# DPPXHK_IO.net
KiCad netlist of a schematic drawn in Altium Designer
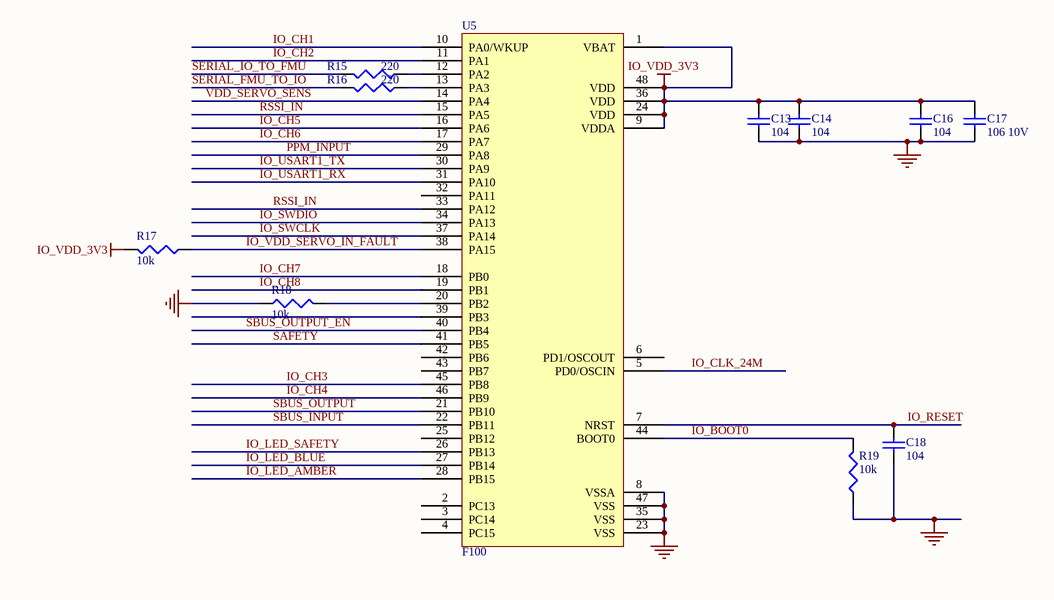
[diagram p0: DPPXHK_IO.SCHDOC]

(export (version "E")
  (design (tool "Eeschema 10.0.6"))
  (components
    (comp (ref "C13")
      (value "104")
      (footprint "LC0402")
      (description "Capacitor (Semiconductor SIM Model)")
      (fields (field (name "PUBLISHER") "Altium Limited"))
      (libsource (lib "Miscellaneous Devices") (part "Cap Semi"))
    )
    (comp (ref "C14")
      (value "104")
      (footprint "LC0402")
      (description "Capacitor (Semiconductor SIM Model)")
      (fields (field (name "PUBLISHER") "Altium Limited"))
      (libsource (lib "Miscellaneous Devices") (part "Cap Semi"))
    )
    (comp (ref "C16")
      (value "104")
      (footprint "LC0402")
      (description "Capacitor (Semiconductor SIM Model)")
      (fields (field (name "PUBLISHER") "Altium Limited"))
      (libsource (lib "Miscellaneous Devices") (part "Cap Semi"))
    )
    (comp (ref "C17")
      (value "106 10V")
      (footprint "LC0402")
      (description "Capacitor (Semiconductor SIM Model)")
      (fields (field (name "PUBLISHER") "Altium Limited"))
      (libsource (lib "Miscellaneous Devices") (part "Cap Semi"))
    )
    (comp (ref "C18")
      (value "104")
      (footprint "LC0402")
      (description "Capacitor (Semiconductor SIM Model)")
      (fields (field (name "PUBLISHER") "Altium Limited"))
      (libsource (lib "Miscellaneous Devices") (part "Cap Semi"))
    )
    (comp (ref "R15")
      (value "220")
      (footprint "0402R")
      (description "Resistor")
      (fields (field (name "PUBLISHER") "Altium Limited"))
      (libsource (lib "Miscellaneous Devices") (part "Res3"))
    )
    (comp (ref "R16")
      (value "220")
      (footprint "0402R")
      (description "Resistor")
      (fields (field (name "PUBLISHER") "Altium Limited"))
      (libsource (lib "Miscellaneous Devices") (part "Res3"))
    )
    (comp (ref "R17")
      (value "10k")
      (footprint "0402R")
      (description "Resistor")
      (fields (field (name "PUBLISHER") "Altium Limited"))
      (libsource (lib "Miscellaneous Devices") (part "Res3"))
    )
    (comp (ref "R18")
      (value "10k")
      (footprint "0402R")
      (description "Resistor")
      (fields (field (name "PUBLISHER") "Altium Limited"))
      (libsource (lib "Miscellaneous Devices") (part "Res3"))
    )
    (comp (ref "R19")
      (value "10k")
      (footprint "0402R")
      (description "Resistor")
      (fields (field (name "PUBLISHER") "Altium Limited"))
      (libsource (lib "Miscellaneous Devices") (part "Res3"))
    )
    (comp (ref "U5") (value "F100") (footprint "LQFP48_ST") (libsource (lib "PXHK") (part "F100")))
  )
  (nets
    (net (code "1") (name "/IO_BOOT0") (class "Default")
      (node (ref "R19") (pin "2") (pinfunction "2_2") (pintype "passive"))
      (node (ref "U5") (pin "44") (pinfunction "BOOT0_44") (pintype "passive"))
    )
    (net (code "2") (name "/IO_CH1") (class "Default")
      (node (ref "U5") (pin "10") (pinfunction "PA0/WKUP_10") (pintype "passive"))
    )
    (net (code "3") (name "/IO_CH2") (class "Default")
      (node (ref "U5") (pin "11") (pinfunction "PA1_11") (pintype "passive"))
    )
    (net (code "4") (name "/IO_CH3") (class "Default")
      (node (ref "U5") (pin "45") (pinfunction "PB8_45") (pintype "passive"))
    )
    (net (code "5") (name "/IO_CH4") (class "Default")
      (node (ref "U5") (pin "46") (pinfunction "PB9_46") (pintype "passive"))
    )
    (net (code "6") (name "/IO_CH5") (class "Default")
      (node (ref "U5") (pin "16") (pinfunction "PA6_16") (pintype "passive"))
    )
    (net (code "7") (name "/IO_CH6") (class "Default")
      (node (ref "U5") (pin "17") (pinfunction "PA7_17") (pintype "passive"))
    )
    (net (code "8") (name "/IO_CH7") (class "Default")
      (node (ref "U5") (pin "18") (pinfunction "PB0_18") (pintype "passive"))
    )
    (net (code "9") (name "/IO_CH8") (class "Default")
      (node (ref "U5") (pin "19") (pinfunction "PB1_19") (pintype "passive"))
    )
    (net (code "10") (name "/IO_CLK_24M") (class "Default")
      (node (ref "U5") (pin "5") (pinfunction "PD0/OSCIN_5") (pintype "passive"))
    )
    (net (code "11") (name "/IO_LED_AMBER") (class "Default")
      (node (ref "U5") (pin "28") (pinfunction "PB15_28") (pintype "passive"))
    )
    (net (code "12") (name "/IO_LED_BLUE") (class "Default")
      (node (ref "U5") (pin "27") (pinfunction "PB14_27") (pintype "passive"))
    )
    (net (code "13") (name "/IO_LED_SAFETY") (class "Default")
      (node (ref "U5") (pin "26") (pinfunction "PB13_26") (pintype "passive"))
    )
    (net (code "14") (name "/IO_RESET") (class "Default")
      (node (ref "C18") (pin "2") (pinfunction "2_2") (pintype "passive"))
      (node (ref "U5") (pin "7") (pinfunction "NRST_7") (pintype "passive"))
    )
    (net (code "15") (name "/IO_SWCLK") (class "Default")
      (node (ref "U5") (pin "37") (pinfunction "PA14_37") (pintype "passive"))
    )
    (net (code "16") (name "/IO_SWDIO") (class "Default")
      (node (ref "U5") (pin "34") (pinfunction "PA13_34") (pintype "passive"))
    )
    (net (code "17") (name "/IO_USART1_RX") (class "Default")
      (node (ref "U5") (pin "31") (pinfunction "PA10_31") (pintype "passive"))
    )
    (net (code "18") (name "/IO_USART1_TX") (class "Default")
      (node (ref "U5") (pin "30") (pinfunction "PA9_30") (pintype "passive"))
    )
    (net (code "19") (name "/IO_VDD_SERVO_IN_FAULT") (class "Default")
      (node (ref "R17") (pin "1") (pinfunction "1_1") (pintype "passive"))
      (node (ref "U5") (pin "38") (pinfunction "PA15_38") (pintype "passive"))
    )
    (net (code "20") (name "/PPM_INPUT") (class "Default")
      (node (ref "U5") (pin "29") (pinfunction "PA8_29") (pintype "passive"))
    )
    (net (code "21") (name "/RSSI_IN") (class "Default")
      (node (ref "U5") (pin "15") (pinfunction "PA5_15") (pintype "passive"))
      (node (ref "U5") (pin "33") (pinfunction "PA12_33") (pintype "passive"))
    )
    (net (code "22") (name "/SAFETY") (class "Default")
      (node (ref "U5") (pin "41") (pinfunction "PB5_41") (pintype "passive"))
    )
    (net (code "23") (name "/SBUS_INPUT") (class "Default")
      (node (ref "U5") (pin "22") (pinfunction "PB11_22") (pintype "passive"))
    )
    (net (code "24") (name "/SBUS_OUTPUT") (class "Default")
      (node (ref "U5") (pin "21") (pinfunction "PB10_21") (pintype "passive"))
    )
    (net (code "25") (name "/SBUS_OUTPUT_EN") (class "Default")
      (node (ref "U5") (pin "40") (pinfunction "PB4_40") (pintype "passive"))
    )
    (net (code "26") (name "/SERIAL_FMU_TO_IO") (class "Default")
      (node (ref "R16") (pin "2") (pinfunction "2_2") (pintype "passive"))
    )
    (net (code "27") (name "/SERIAL_IO_TO_FMU") (class "Default")
      (node (ref "R15") (pin "2") (pinfunction "2_2") (pintype "passive"))
    )
    (net (code "28") (name "/VDD_SERVO_SENS") (class "Default")
      (node (ref "U5") (pin "14") (pinfunction "PA4_14") (pintype "passive"))
    )
    (net (code "29") (name "GND") (class "Default")
      (node (ref "C13") (pin "2") (pinfunction "2_2") (pintype "passive"))
      (node (ref "C14") (pin "2") (pinfunction "2_2") (pintype "passive"))
      (node (ref "C16") (pin "2") (pinfunction "2_2") (pintype "passive"))
      (node (ref "C17") (pin "2") (pinfunction "2_2") (pintype "passive"))
      (node (ref "C18") (pin "1") (pinfunction "1_1") (pintype "passive"))
      (node (ref "R18") (pin "1") (pinfunction "1_1") (pintype "passive"))
      (node (ref "R19") (pin "1") (pinfunction "1_1") (pintype "passive"))
      (node (ref "U5") (pin "23") (pinfunction "VSS_23") (pintype "passive"))
      (node (ref "U5") (pin "35") (pinfunction "VSS_35") (pintype "passive"))
      (node (ref "U5") (pin "47") (pinfunction "VSS_47") (pintype "passive"))
      (node (ref "U5") (pin "8") (pinfunction "VSSA_8") (pintype "passive"))
    )
    (net (code "30") (name "IO_VDD_3V3") (class "Default")
      (node (ref "C13") (pin "1") (pinfunction "1_1") (pintype "passive"))
      (node (ref "C14") (pin "1") (pinfunction "1_1") (pintype "passive"))
      (node (ref "C16") (pin "1") (pinfunction "1_1") (pintype "passive"))
      (node (ref "C17") (pin "1") (pinfunction "1_1") (pintype "passive"))
      (node (ref "R17") (pin "2") (pinfunction "2_2") (pintype "passive"))
      (node (ref "U5") (pin "1") (pinfunction "VBAT_1") (pintype "passive"))
      (node (ref "U5") (pin "24") (pinfunction "VDD_24") (pintype "passive"))
      (node (ref "U5") (pin "36") (pinfunction "VDD_36") (pintype "passive"))
      (node (ref "U5") (pin "48") (pinfunction "VDD_48") (pintype "passive"))
      (node (ref "U5") (pin "9") (pinfunction "VDDA_9") (pintype "passive"))
    )
    (net (code "31") (name "Net-(U5-PA2)") (class "Default")
      (node (ref "R15") (pin "1") (pinfunction "1_1") (pintype "passive"))
      (node (ref "U5") (pin "12") (pinfunction "PA2_12") (pintype "passive"))
    )
    (net (code "32") (name "Net-(U5-PA3)") (class "Default")
      (node (ref "R16") (pin "1") (pinfunction "1_1") (pintype "passive"))
      (node (ref "U5") (pin "13") (pinfunction "PA3_13") (pintype "passive"))
    )
    (net (code "33") (name "Net-(U5-PB2)") (class "Default")
      (node (ref "R18") (pin "2") (pinfunction "2_2") (pintype "passive"))
      (node (ref "U5") (pin "20") (pinfunction "PB2_20") (pintype "passive"))
    )
    (net (code "34") (name "unconnected-(U5-PA11-Pad32)") (class "Default")
      (node (ref "U5") (pin "32") (pinfunction "PA11_32") (pintype "passive"))
    )
    (net (code "35") (name "unconnected-(U5-PB3-Pad39)") (class "Default")
      (node (ref "U5") (pin "39") (pinfunction "PB3_39") (pintype "passive"))
    )
    (net (code "36") (name "unconnected-(U5-PB6-Pad42)") (class "Default")
      (node (ref "U5") (pin "42") (pinfunction "PB6_42") (pintype "passive"))
    )
    (net (code "37") (name "unconnected-(U5-PB7-Pad43)") (class "Default")
      (node (ref "U5") (pin "43") (pinfunction "PB7_43") (pintype "passive"))
    )
    (net (code "38") (name "unconnected-(U5-PB12-Pad25)") (class "Default")
      (node (ref "U5") (pin "25") (pinfunction "PB12_25") (pintype "passive"))
    )
    (net (code "39") (name "unconnected-(U5-PC13-Pad2)") (class "Default")
      (node (ref "U5") (pin "2") (pinfunction "PC13_2") (pintype "passive"))
    )
    (net (code "40") (name "unconnected-(U5-PC14-Pad3)") (class "Default")
      (node (ref "U5") (pin "3") (pinfunction "PC14_3") (pintype "passive"))
    )
    (net (code "41") (name "unconnected-(U5-PC15-Pad4)") (class "Default")
      (node (ref "U5") (pin "4") (pinfunction "PC15_4") (pintype "passive"))
    )
    (net (code "42") (name "unconnected-(U5-PD1{slash}OSCOUT-Pad6)") (class "Default")
      (node (ref "U5") (pin "6") (pinfunction "PD1/OSCOUT_6") (pintype "passive"))
    )
  )
)
